# tomato-single-cell.net
KiCad netlist of a schematic drawn in EAGLE
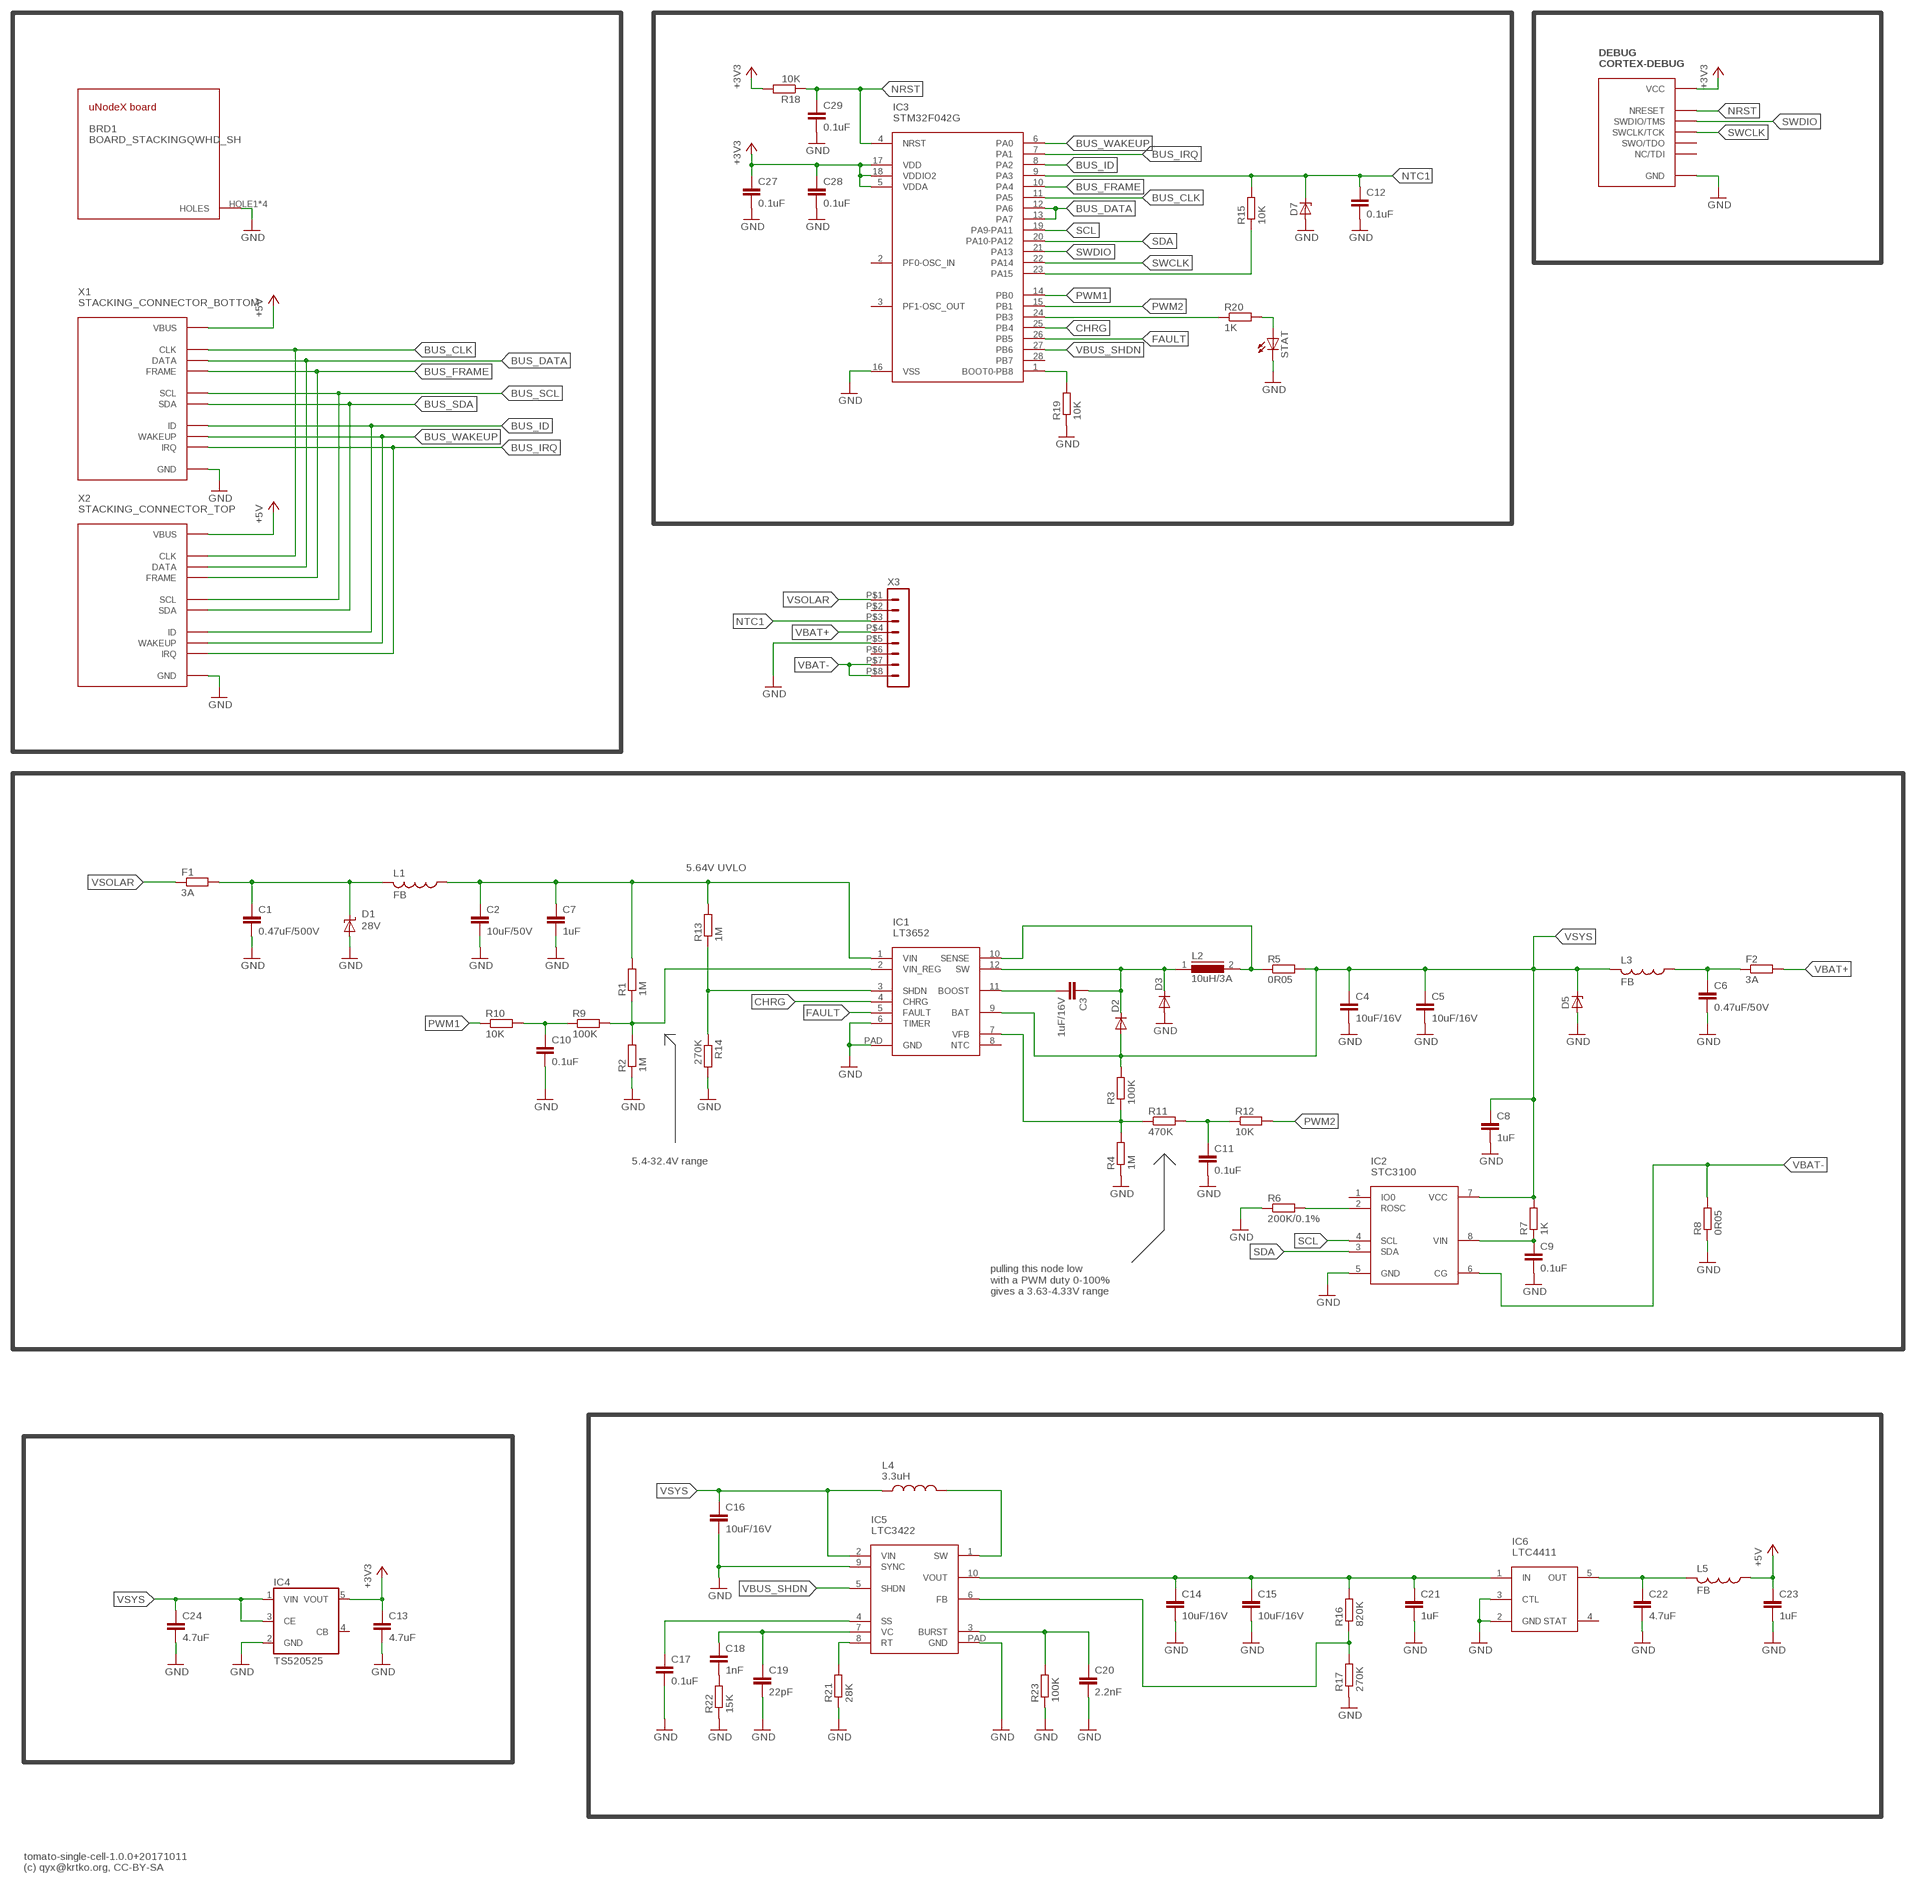
[diagram p0: schematic, sheet 1]

(export (version "E")
  (design (tool "Eeschema 10.0.6"))
  (components
    (comp (ref "BRD1")
      (value "BOARD_STACKINGQWHD_SH")
      (footprint "eagle-import:QWHD_SHARP_CORNERS")
      (libsource (lib "eagle-import") (part "BOARD_STACKINGQWHD_SH"))
    )
    (comp (ref "C1")
      (value "0.47uF/500V")
      (footprint "eagle-import:C1206")
      (libsource (lib "eagle-import") (part "C-EUC1206"))
    )
    (comp (ref "C2")
      (value "10uF/50V")
      (footprint "eagle-import:C2220K")
      (libsource (lib "eagle-import") (part "C-EUC2220K"))
    )
    (comp (ref "C3")
      (value "1uF/16V")
      (footprint "eagle-import:C0805")
      (libsource (lib "eagle-import") (part "C-EUC0805"))
    )
    (comp (ref "C4")
      (value "10uF/16V")
      (footprint "eagle-import:C1206")
      (libsource (lib "eagle-import") (part "C-EUC1206"))
    )
    (comp (ref "C5")
      (value "10uF/16V")
      (footprint "eagle-import:C1206")
      (libsource (lib "eagle-import") (part "C-EUC1206"))
    )
    (comp (ref "C6")
      (value "0.47uF/50V")
      (footprint "eagle-import:C0805")
      (libsource (lib "eagle-import") (part "C-EUC0805"))
    )
    (comp (ref "C7")
      (value "1uF")
      (footprint "eagle-import:C0805")
      (libsource (lib "eagle-import") (part "C-EUC0805"))
    )
    (comp (ref "C8")
      (value "1uF")
      (footprint "eagle-import:C0603")
      (libsource (lib "eagle-import") (part "C-EUC0603"))
    )
    (comp (ref "C9")
      (value "0.1uF")
      (footprint "eagle-import:C0603")
      (libsource (lib "eagle-import") (part "C-EUC0603"))
    )
    (comp (ref "C10")
      (value "0.1uF")
      (footprint "eagle-import:C0603")
      (libsource (lib "eagle-import") (part "C-EUC0603"))
    )
    (comp (ref "C11")
      (value "0.1uF")
      (footprint "eagle-import:C0603")
      (libsource (lib "eagle-import") (part "C-EUC0603"))
    )
    (comp (ref "C12")
      (value "0.1uF")
      (footprint "eagle-import:C0603")
      (libsource (lib "eagle-import") (part "C-EUC0603"))
    )
    (comp (ref "C13")
      (value "4.7uF")
      (footprint "eagle-import:C0805")
      (libsource (lib "eagle-import") (part "C-EUC0805"))
    )
    (comp (ref "C14")
      (value "10uF/16V")
      (footprint "eagle-import:C1206")
      (libsource (lib "eagle-import") (part "C-EUC1206"))
    )
    (comp (ref "C15")
      (value "10uF/16V")
      (footprint "eagle-import:C1206")
      (libsource (lib "eagle-import") (part "C-EUC1206"))
    )
    (comp (ref "C16")
      (value "10uF/16V")
      (footprint "eagle-import:C1206")
      (libsource (lib "eagle-import") (part "C-EUC1206"))
    )
    (comp (ref "C17")
      (value "0.1uF")
      (footprint "eagle-import:C0603")
      (libsource (lib "eagle-import") (part "C-EUC0603"))
    )
    (comp (ref "C18")
      (value "1nF")
      (footprint "eagle-import:C0603")
      (libsource (lib "eagle-import") (part "C-EUC0603"))
    )
    (comp (ref "C19")
      (value "22pF")
      (footprint "eagle-import:C0603")
      (libsource (lib "eagle-import") (part "C-EUC0603"))
    )
    (comp (ref "C20")
      (value "2.2nF")
      (footprint "eagle-import:C0603")
      (libsource (lib "eagle-import") (part "C-EUC0603"))
    )
    (comp (ref "C21")
      (value "1uF")
      (footprint "eagle-import:C0805")
      (libsource (lib "eagle-import") (part "C-EUC0805"))
    )
    (comp (ref "C22")
      (value "4.7uF")
      (footprint "eagle-import:C0805")
      (libsource (lib "eagle-import") (part "C-EUC0805"))
    )
    (comp (ref "C23")
      (value "1uF")
      (footprint "eagle-import:C0805")
      (libsource (lib "eagle-import") (part "C-EUC0805"))
    )
    (comp (ref "C24")
      (value "4.7uF")
      (footprint "eagle-import:C0805")
      (libsource (lib "eagle-import") (part "C-EUC0805"))
    )
    (comp (ref "C27")
      (value "0.1uF")
      (footprint "eagle-import:C0603")
      (libsource (lib "eagle-import") (part "C-EUC0603"))
    )
    (comp (ref "C28")
      (value "0.1uF")
      (footprint "eagle-import:C0603")
      (libsource (lib "eagle-import") (part "C-EUC0603"))
    )
    (comp (ref "C29")
      (value "0.1uF")
      (footprint "eagle-import:C0603")
      (libsource (lib "eagle-import") (part "C-EUC0603"))
    )
    (comp (ref "D1")
      (value "28V")
      (footprint "eagle-import:SMBJ")
      (libsource (lib "eagle-import") (part "SUPPRESSOR-SMBJ"))
    )
    (comp (ref "D2")
      (value "DIODE-SOD323-W")
      (footprint "eagle-import:SOD323-W")
      (libsource (lib "eagle-import") (part "DIODE-SOD323-W"))
    )
    (comp (ref "D3")
      (value "DIODE-SOD323-W")
      (footprint "eagle-import:SOD323-W")
      (libsource (lib "eagle-import") (part "DIODE-SOD323-W"))
    )
    (comp (ref "D5")
      (value "ZENER-DIODESOT23")
      (footprint "eagle-import:SOT23")
      (libsource (lib "eagle-import") (part "ZENER-DIODESOT23"))
    )
    (comp (ref "D7")
      (value "ZENER-DIODESOT23")
      (footprint "eagle-import:SOT23")
      (libsource (lib "eagle-import") (part "ZENER-DIODESOT23"))
    )
    (comp (ref "DEBUG")
      (value "CORTEX-DEBUG")
      (footprint "eagle-import:CORTEX-DEBUG")
      (libsource (lib "eagle-import") (part "CORTEX-DEBUG"))
    )
    (comp (ref "F1")
      (value "3A")
      (footprint "eagle-import:R1206")
      (libsource (lib "eagle-import") (part "R-EU_R1206"))
    )
    (comp (ref "F2")
      (value "3A")
      (footprint "eagle-import:R1206")
      (libsource (lib "eagle-import") (part "R-EU_R1206"))
    )
    (comp (ref "IC1")
      (value "LT3652")
      (footprint "eagle-import:MSOP12-PAD")
      (libsource (lib "eagle-import") (part "LT3652"))
    )
    (comp (ref "IC2")
      (value "STC3100")
      (footprint "eagle-import:MSOP8")
      (libsource (lib "eagle-import") (part "STC3100"))
    )
    (comp (ref "IC3")
      (value "STM32F042G")
      (footprint "eagle-import:UFQFPN28")
      (libsource (lib "eagle-import") (part "STM32F042G"))
    )
    (comp (ref "IC4")
      (value "TS520525")
      (footprint "eagle-import:SOT25")
      (libsource (lib "eagle-import") (part "TS520525"))
    )
    (comp (ref "IC5")
      (value "LTC3422")
      (footprint "eagle-import:DFN10-3X3")
      (libsource (lib "eagle-import") (part "LTC3422"))
    )
    (comp (ref "IC6")
      (value "LTC4411")
      (footprint "eagle-import:SOT23-5")
      (libsource (lib "eagle-import") (part "LTC4411"))
    )
    (comp (ref "L1")
      (value "FB")
      (footprint "eagle-import:L3216C")
      (libsource (lib "eagle-import") (part "L-USL3216C"))
    )
    (comp (ref "L2")
      (value "10uH/3A")
      (footprint "eagle-import:DR74")
      (libsource (lib "eagle-import") (part "DR74"))
    )
    (comp (ref "L3")
      (value "FB")
      (footprint "eagle-import:L3216C")
      (libsource (lib "eagle-import") (part "L-USL3216C"))
    )
    (comp (ref "L4")
      (value "3.3uH")
      (footprint "eagle-import:XAL50XX")
      (libsource (lib "eagle-import") (part "XAL50XX"))
    )
    (comp (ref "L5")
      (value "FB")
      (footprint "eagle-import:L3216C")
      (libsource (lib "eagle-import") (part "L-USL3216C"))
    )
    (comp (ref "R1")
      (value "1M")
      (footprint "eagle-import:R0603")
      (libsource (lib "eagle-import") (part "R-EU_R0603"))
    )
    (comp (ref "R2")
      (value "1M")
      (footprint "eagle-import:R0603")
      (libsource (lib "eagle-import") (part "R-EU_R0603"))
    )
    (comp (ref "R3")
      (value "100K")
      (footprint "eagle-import:R0603")
      (libsource (lib "eagle-import") (part "R-EU_R0603"))
    )
    (comp (ref "R4")
      (value "1M")
      (footprint "eagle-import:R0603")
      (libsource (lib "eagle-import") (part "R-EU_R0603"))
    )
    (comp (ref "R5")
      (value "0R05")
      (footprint "eagle-import:R1206")
      (libsource (lib "eagle-import") (part "R-EU_R1206"))
    )
    (comp (ref "R6")
      (value "200K/0.1%")
      (footprint "eagle-import:R0603")
      (libsource (lib "eagle-import") (part "R-EU_R0603"))
    )
    (comp (ref "R7")
      (value "1K")
      (footprint "eagle-import:R0603")
      (libsource (lib "eagle-import") (part "R-EU_R0603"))
    )
    (comp (ref "R8")
      (value "0R05")
      (footprint "eagle-import:R1206")
      (libsource (lib "eagle-import") (part "R-EU_R1206"))
    )
    (comp (ref "R9")
      (value "100K")
      (footprint "eagle-import:R0603")
      (libsource (lib "eagle-import") (part "R-EU_R0603"))
    )
    (comp (ref "R10")
      (value "10K")
      (footprint "eagle-import:R0603")
      (libsource (lib "eagle-import") (part "R-EU_R0603"))
    )
    (comp (ref "R11")
      (value "470K")
      (footprint "eagle-import:R0603")
      (libsource (lib "eagle-import") (part "R-EU_R0603"))
    )
    (comp (ref "R12")
      (value "10K")
      (footprint "eagle-import:R0603")
      (libsource (lib "eagle-import") (part "R-EU_R0603"))
    )
    (comp (ref "R13")
      (value "1M")
      (footprint "eagle-import:R0603")
      (libsource (lib "eagle-import") (part "R-EU_R0603"))
    )
    (comp (ref "R14")
      (value "270K")
      (footprint "eagle-import:R0603")
      (libsource (lib "eagle-import") (part "R-EU_R0603"))
    )
    (comp (ref "R15")
      (value "10K")
      (footprint "eagle-import:R0603")
      (libsource (lib "eagle-import") (part "R-EU_R0603"))
    )
    (comp (ref "R16")
      (value "820K")
      (footprint "eagle-import:R0603")
      (libsource (lib "eagle-import") (part "R-EU_R0603"))
    )
    (comp (ref "R17")
      (value "270K")
      (footprint "eagle-import:R0603")
      (libsource (lib "eagle-import") (part "R-EU_R0603"))
    )
    (comp (ref "R18")
      (value "10K")
      (footprint "eagle-import:R0603")
      (libsource (lib "eagle-import") (part "R-EU_R0603"))
    )
    (comp (ref "R19")
      (value "10K")
      (footprint "eagle-import:R0603")
      (libsource (lib "eagle-import") (part "R-EU_R0603"))
    )
    (comp (ref "R20")
      (value "1K")
      (footprint "eagle-import:R0603")
      (libsource (lib "eagle-import") (part "R-EU_R0603"))
    )
    (comp (ref "R21")
      (value "28K")
      (footprint "eagle-import:R0603")
      (libsource (lib "eagle-import") (part "R-EU_R0603"))
    )
    (comp (ref "R22")
      (value "15K")
      (footprint "eagle-import:R0603")
      (libsource (lib "eagle-import") (part "R-EU_R0603"))
    )
    (comp (ref "R23")
      (value "100K")
      (footprint "eagle-import:R0603")
      (libsource (lib "eagle-import") (part "R-EU_R0603"))
    )
    (comp (ref "STAT")
      (value "LEDCHIPLED_0805")
      (footprint "eagle-import:CHIPLED_0805")
      (libsource (lib "eagle-import") (part "LEDCHIPLED_0805"))
    )
    (comp (ref "X1")
      (value "STACKING_CONNECTOR_BOTTOM")
      (footprint "eagle-import:HAR-FLEX-BOTTOM-12P")
      (libsource (lib "eagle-import") (part "STACKING_CONNECTOR_BOTTOM"))
    )
    (comp (ref "X2")
      (value "STACKING_CONNECTOR_TOP")
      (footprint "eagle-import:HAR-FLEX-TOP-12P")
      (libsource (lib "eagle-import") (part "STACKING_CONNECTOR_TOP"))
    )
    (comp (ref "X3")
      (value "HEADER_POS8_43045-0800")
      (footprint "eagle-import:43045-0800")
      (libsource (lib "eagle-import") (part "HEADER_POS8_?43045-0800"))
    )
  )
  (nets
    (net (code "1") (name "+3V3") (class "Default")
      (node (ref "C13") (pin "1") (pinfunction "1_1") (pintype "passive"))
      (node (ref "C27") (pin "1") (pinfunction "1_1") (pintype "passive"))
      (node (ref "C28") (pin "1") (pinfunction "1_1") (pintype "passive"))
      (node (ref "DEBUG") (pin "VCC") (pinfunction "VCC_VCC") (pintype "bidirectional"))
      (node (ref "IC3") (pin "17") (pinfunction "VDD_17") (pintype "bidirectional"))
      (node (ref "IC3") (pin "18") (pinfunction "VDDIO2_18") (pintype "bidirectional"))
      (node (ref "IC3") (pin "5") (pinfunction "VDDA_5") (pintype "bidirectional"))
      (node (ref "IC4") (pin "5") (pinfunction "VOUT_5") (pintype "passive"))
      (node (ref "R18") (pin "2") (pinfunction "2_2") (pintype "passive"))
    )
    (net (code "2") (name "+5V") (class "Default")
      (node (ref "C23") (pin "1") (pinfunction "1_1") (pintype "passive"))
      (node (ref "L5") (pin "1") (pinfunction "1_1") (pintype "passive"))
      (node (ref "X1") (pin "VBUS") (pinfunction "VBUS_VBUS") (pintype "bidirectional"))
      (node (ref "X2") (pin "VBUS") (pinfunction "VBUS_VBUS") (pintype "bidirectional"))
    )
    (net (code "3") (name "BUS_CLK") (class "Default")
      (node (ref "IC3") (pin "11") (pinfunction "PA5_11") (pintype "bidirectional"))
      (node (ref "X1") (pin "CLK") (pinfunction "CLK_CLK") (pintype "bidirectional"))
      (node (ref "X2") (pin "CLK") (pinfunction "CLK_CLK") (pintype "bidirectional"))
    )
    (net (code "4") (name "BUS_DATA") (class "Default")
      (node (ref "IC3") (pin "12") (pinfunction "PA6_12") (pintype "bidirectional"))
      (node (ref "IC3") (pin "13") (pinfunction "PA7_13") (pintype "bidirectional"))
      (node (ref "X1") (pin "DATA") (pinfunction "DATA_DATA") (pintype "bidirectional"))
      (node (ref "X2") (pin "DATA") (pinfunction "DATA_DATA") (pintype "bidirectional"))
    )
    (net (code "5") (name "BUS_FRAME") (class "Default")
      (node (ref "IC3") (pin "10") (pinfunction "PA4_10") (pintype "bidirectional"))
      (node (ref "X1") (pin "FRAME") (pinfunction "FRAME_FRAME") (pintype "bidirectional"))
      (node (ref "X2") (pin "FRAME") (pinfunction "FRAME_FRAME") (pintype "bidirectional"))
    )
    (net (code "6") (name "BUS_ID") (class "Default")
      (node (ref "IC3") (pin "8") (pinfunction "PA2_8") (pintype "bidirectional"))
      (node (ref "X1") (pin "ID") (pinfunction "ID_ID") (pintype "bidirectional"))
      (node (ref "X2") (pin "ID") (pinfunction "ID_ID") (pintype "bidirectional"))
    )
    (net (code "7") (name "BUS_IRQ") (class "Default")
      (node (ref "IC3") (pin "7") (pinfunction "PA1_7") (pintype "bidirectional"))
      (node (ref "X1") (pin "IRQ") (pinfunction "IRQ_IRQ") (pintype "bidirectional"))
      (node (ref "X2") (pin "IRQ") (pinfunction "IRQ_IRQ") (pintype "bidirectional"))
    )
    (net (code "8") (name "BUS_SCL") (class "Default")
      (node (ref "X1") (pin "SCL") (pinfunction "SCL_SCL") (pintype "bidirectional"))
      (node (ref "X2") (pin "SCL") (pinfunction "SCL_SCL") (pintype "bidirectional"))
    )
    (net (code "9") (name "BUS_SDA") (class "Default")
      (node (ref "X1") (pin "SDA") (pinfunction "SDA_SDA") (pintype "bidirectional"))
      (node (ref "X2") (pin "SDA") (pinfunction "SDA_SDA") (pintype "bidirectional"))
    )
    (net (code "10") (name "BUS_WAKEUP") (class "Default")
      (node (ref "IC3") (pin "6") (pinfunction "PA0_6") (pintype "bidirectional"))
      (node (ref "X1") (pin "WAKEUP") (pinfunction "WAKEUP_WAKEUP") (pintype "bidirectional"))
      (node (ref "X2") (pin "WAKEUP") (pinfunction "WAKEUP_WAKEUP") (pintype "bidirectional"))
    )
    (net (code "11") (name "CHRG") (class "Default")
      (node (ref "IC1") (pin "4") (pinfunction "CHRG_4") (pintype "bidirectional"))
      (node (ref "IC3") (pin "25") (pinfunction "PB4_25") (pintype "bidirectional"))
    )
    (net (code "12") (name "FAULT") (class "Default")
      (node (ref "IC1") (pin "5") (pinfunction "FAULT_5") (pintype "bidirectional"))
      (node (ref "IC3") (pin "26") (pinfunction "PB5_26") (pintype "bidirectional"))
    )
    (net (code "13") (name "GND") (class "Default")
      (node (ref "BRD1") (pin "HOLE1") (pinfunction "HOLES_HOLE1") (pintype "bidirectional"))
      (node (ref "BRD1") (pin "HOLE2") (pinfunction "HOLES_HOLE2") (pintype "bidirectional"))
      (node (ref "BRD1") (pin "HOLE3") (pinfunction "HOLES_HOLE3") (pintype "bidirectional"))
      (node (ref "BRD1") (pin "HOLE4") (pinfunction "HOLES_HOLE4") (pintype "bidirectional"))
      (node (ref "C1") (pin "2") (pinfunction "2_2") (pintype "passive"))
      (node (ref "C10") (pin "2") (pinfunction "2_2") (pintype "passive"))
      (node (ref "C11") (pin "2") (pinfunction "2_2") (pintype "passive"))
      (node (ref "C12") (pin "2") (pinfunction "2_2") (pintype "passive"))
      (node (ref "C13") (pin "2") (pinfunction "2_2") (pintype "passive"))
      (node (ref "C14") (pin "2") (pinfunction "2_2") (pintype "passive"))
      (node (ref "C15") (pin "2") (pinfunction "2_2") (pintype "passive"))
      (node (ref "C16") (pin "2") (pinfunction "2_2") (pintype "passive"))
      (node (ref "C17") (pin "2") (pinfunction "2_2") (pintype "passive"))
      (node (ref "C19") (pin "2") (pinfunction "2_2") (pintype "passive"))
      (node (ref "C2") (pin "2") (pinfunction "2_2") (pintype "passive"))
      (node (ref "C20") (pin "2") (pinfunction "2_2") (pintype "passive"))
      (node (ref "C21") (pin "2") (pinfunction "2_2") (pintype "passive"))
      (node (ref "C22") (pin "2") (pinfunction "2_2") (pintype "passive"))
      (node (ref "C23") (pin "2") (pinfunction "2_2") (pintype "passive"))
      (node (ref "C24") (pin "2") (pinfunction "2_2") (pintype "passive"))
      (node (ref "C27") (pin "2") (pinfunction "2_2") (pintype "passive"))
      (node (ref "C28") (pin "2") (pinfunction "2_2") (pintype "passive"))
      (node (ref "C29") (pin "2") (pinfunction "2_2") (pintype "passive"))
      (node (ref "C4") (pin "2") (pinfunction "2_2") (pintype "passive"))
      (node (ref "C5") (pin "2") (pinfunction "2_2") (pintype "passive"))
      (node (ref "C6") (pin "2") (pinfunction "2_2") (pintype "passive"))
      (node (ref "C7") (pin "2") (pinfunction "2_2") (pintype "passive"))
      (node (ref "C8") (pin "2") (pinfunction "2_2") (pintype "passive"))
      (node (ref "C9") (pin "2") (pinfunction "2_2") (pintype "passive"))
      (node (ref "D1") (pin "A") (pinfunction "A_A") (pintype "passive"))
      (node (ref "D3") (pin "A") (pinfunction "A_A") (pintype "passive"))
      (node (ref "D5") (pin "1") (pinfunction "A_1") (pintype "passive"))
      (node (ref "D7") (pin "1") (pinfunction "A_1") (pintype "passive"))
      (node (ref "DEBUG") (pin "GND1") (pinfunction "GND_GND1") (pintype "bidirectional"))
      (node (ref "DEBUG") (pin "GND2") (pinfunction "GND_GND2") (pintype "bidirectional"))
      (node (ref "DEBUG") (pin "GND_DETECT") (pinfunction "GND_GND_DETECT") (pintype "bidirectional"))
      (node (ref "IC1") (pin "6") (pinfunction "TIMER_6") (pintype "bidirectional"))
      (node (ref "IC1") (pin "PAD") (pinfunction "GND_PAD") (pintype "bidirectional"))
      (node (ref "IC2") (pin "5") (pinfunction "GND_5") (pintype "power_in"))
      (node (ref "IC3") (pin "16") (pinfunction "VSS_16") (pintype "bidirectional"))
      (node (ref "IC4") (pin "2") (pinfunction "GND_2") (pintype "passive"))
      (node (ref "IC5") (pin "9") (pinfunction "SYNC_9") (pintype "bidirectional"))
      (node (ref "IC5") (pin "PAD") (pinfunction "GND_PAD") (pintype "bidirectional"))
      (node (ref "IC6") (pin "2") (pinfunction "GND_2") (pintype "bidirectional"))
      (node (ref "IC6") (pin "3") (pinfunction "CTL_3") (pintype "bidirectional"))
      (node (ref "R14") (pin "2") (pinfunction "2_2") (pintype "passive"))
      (node (ref "R17") (pin "1") (pinfunction "1_1") (pintype "passive"))
      (node (ref "R19") (pin "1") (pinfunction "1_1") (pintype "passive"))
      (node (ref "R2") (pin "1") (pinfunction "1_1") (pintype "passive"))
      (node (ref "R21") (pin "1") (pinfunction "1_1") (pintype "passive"))
      (node (ref "R22") (pin "1") (pinfunction "1_1") (pintype "passive"))
      (node (ref "R23") (pin "1") (pinfunction "1_1") (pintype "passive"))
      (node (ref "R4") (pin "1") (pinfunction "1_1") (pintype "passive"))
      (node (ref "R6") (pin "1") (pinfunction "1_1") (pintype "passive"))
      (node (ref "R8") (pin "1") (pinfunction "1_1") (pintype "passive"))
      (node (ref "STAT") (pin "C") (pinfunction "C_C") (pintype "passive"))
      (node (ref "X1") (pin "GND1") (pinfunction "GND_GND1") (pintype "bidirectional"))
      (node (ref "X1") (pin "GND2") (pinfunction "GND_GND2") (pintype "bidirectional"))
      (node (ref "X1") (pin "GND3") (pinfunction "GND_GND3") (pintype "bidirectional"))
      (node (ref "X1") (pin "H1") (pinfunction "GND_H1") (pintype "bidirectional"))
      (node (ref "X1") (pin "H2") (pinfunction "GND_H2") (pintype "bidirectional"))
      (node (ref "X1") (pin "H3") (pinfunction "GND_H3") (pintype "bidirectional"))
      (node (ref "X1") (pin "H4") (pinfunction "GND_H4") (pintype "bidirectional"))
      (node (ref "X2") (pin "GND1") (pinfunction "GND_GND1") (pintype "bidirectional"))
      (node (ref "X2") (pin "GND2") (pinfunction "GND_GND2") (pintype "bidirectional"))
      (node (ref "X2") (pin "GND3") (pinfunction "GND_GND3") (pintype "bidirectional"))
      (node (ref "X2") (pin "H1") (pinfunction "GND_H1") (pintype "bidirectional"))
      (node (ref "X2") (pin "H2") (pinfunction "GND_H2") (pintype "bidirectional"))
      (node (ref "X2") (pin "H3") (pinfunction "GND_H3") (pintype "bidirectional"))
      (node (ref "X2") (pin "H4") (pinfunction "GND_H4") (pintype "bidirectional"))
      (node (ref "X3") (pin "P$5") (pinfunction "5_P$5") (pintype "passive"))
    )
    (net (code "14") (name "NRST") (class "Default")
      (node (ref "C29") (pin "1") (pinfunction "1_1") (pintype "passive"))
      (node (ref "DEBUG") (pin "NRESET") (pinfunction "NRESET_NRESET") (pintype "bidirectional"))
      (node (ref "IC3") (pin "4") (pinfunction "NRST_4") (pintype "bidirectional"))
      (node (ref "R18") (pin "1") (pinfunction "1_1") (pintype "passive"))
    )
    (net (code "15") (name "NTC1") (class "Default")
      (node (ref "C12") (pin "1") (pinfunction "1_1") (pintype "passive"))
      (node (ref "D7") (pin "3") (pinfunction "C_3") (pintype "passive"))
      (node (ref "IC3") (pin "9") (pinfunction "PA3_9") (pintype "bidirectional"))
      (node (ref "R15") (pin "2") (pinfunction "2_2") (pintype "passive"))
      (node (ref "X3") (pin "P$3") (pinfunction "3_P$3") (pintype "passive"))
    )
    (net (code "16") (name "Net-(C1-Pad1)") (class "Default")
      (node (ref "C1") (pin "1") (pinfunction "1_1") (pintype "passive"))
      (node (ref "D1") (pin "C") (pinfunction "C_C") (pintype "passive"))
      (node (ref "F1") (pin "2") (pinfunction "2_2") (pintype "passive"))
      (node (ref "L1") (pin "2") (pinfunction "2_2") (pintype "passive"))
    )
    (net (code "17") (name "Net-(C6-Pad1)") (class "Default")
      (node (ref "C6") (pin "1") (pinfunction "1_1") (pintype "passive"))
      (node (ref "F2") (pin "1") (pinfunction "1_1") (pintype "passive"))
      (node (ref "L3") (pin "1") (pinfunction "1_1") (pintype "passive"))
    )
    (net (code "18") (name "Net-(C10-Pad1)") (class "Default")
      (node (ref "C10") (pin "1") (pinfunction "1_1") (pintype "passive"))
      (node (ref "R10") (pin "2") (pinfunction "2_2") (pintype "passive"))
      (node (ref "R9") (pin "1") (pinfunction "1_1") (pintype "passive"))
    )
    (net (code "19") (name "Net-(C11-Pad1)") (class "Default")
      (node (ref "C11") (pin "1") (pinfunction "1_1") (pintype "passive"))
      (node (ref "R11") (pin "2") (pinfunction "2_2") (pintype "passive"))
      (node (ref "R12") (pin "1") (pinfunction "1_1") (pintype "passive"))
    )
    (net (code "20") (name "Net-(C18-Pad2)") (class "Default")
      (node (ref "C18") (pin "2") (pinfunction "2_2") (pintype "passive"))
      (node (ref "R22") (pin "2") (pinfunction "2_2") (pintype "passive"))
    )
    (net (code "21") (name "Net-(IC1-BOOST)") (class "Default")
      (node (ref "C3") (pin "2") (pinfunction "2_2") (pintype "passive"))
      (node (ref "IC1") (pin "11") (pinfunction "BOOST_11") (pintype "bidirectional"))
    )
    (net (code "22") (name "Net-(IC1-SENSE)") (class "Default")
      (node (ref "IC1") (pin "10") (pinfunction "SENSE_10") (pintype "bidirectional"))
      (node (ref "L2") (pin "2") (pinfunction "2_2") (pintype "passive"))
      (node (ref "R5") (pin "1") (pinfunction "1_1") (pintype "passive"))
    )
    (net (code "23") (name "Net-(IC1-SHDN)") (class "Default")
      (node (ref "IC1") (pin "3") (pinfunction "SHDN_3") (pintype "bidirectional"))
      (node (ref "R13") (pin "1") (pinfunction "1_1") (pintype "passive"))
      (node (ref "R14") (pin "1") (pinfunction "1_1") (pintype "passive"))
    )
    (net (code "24") (name "Net-(IC1-SW)") (class "Default")
      (node (ref "C3") (pin "1") (pinfunction "1_1") (pintype "passive"))
      (node (ref "D2") (pin "C") (pinfunction "C_C") (pintype "passive"))
      (node (ref "D3") (pin "C") (pinfunction "C_C") (pintype "passive"))
      (node (ref "IC1") (pin "12") (pinfunction "SW_12") (pintype "bidirectional"))
      (node (ref "L2") (pin "1") (pinfunction "1_1") (pintype "passive"))
    )
    (net (code "25") (name "Net-(IC1-VFB)") (class "Default")
      (node (ref "IC1") (pin "7") (pinfunction "VFB_7") (pintype "bidirectional"))
      (node (ref "R11") (pin "1") (pinfunction "1_1") (pintype "passive"))
      (node (ref "R3") (pin "1") (pinfunction "1_1") (pintype "passive"))
      (node (ref "R4") (pin "2") (pinfunction "2_2") (pintype "passive"))
    )
    (net (code "26") (name "Net-(IC1-VIN)") (class "Default")
      (node (ref "C2") (pin "1") (pinfunction "1_1") (pintype "passive"))
      (node (ref "C7") (pin "1") (pinfunction "1_1") (pintype "passive"))
      (node (ref "IC1") (pin "1") (pinfunction "VIN_1") (pintype "bidirectional"))
      (node (ref "L1") (pin "1") (pinfunction "1_1") (pintype "passive"))
      (node (ref "R1") (pin "2") (pinfunction "2_2") (pintype "passive"))
      (node (ref "R13") (pin "2") (pinfunction "2_2") (pintype "passive"))
    )
    (net (code "27") (name "Net-(IC1-VIN_REG)") (class "Default")
      (node (ref "IC1") (pin "2") (pinfunction "VIN_REG_2") (pintype "bidirectional"))
      (node (ref "R1") (pin "1") (pinfunction "1_1") (pintype "passive"))
      (node (ref "R2") (pin "2") (pinfunction "2_2") (pintype "passive"))
      (node (ref "R9") (pin "2") (pinfunction "2_2") (pintype "passive"))
    )
    (net (code "28") (name "Net-(IC2-ROSC)") (class "Default")
      (node (ref "IC2") (pin "2") (pinfunction "ROSC_2") (pintype "bidirectional"))
      (node (ref "R6") (pin "2") (pinfunction "2_2") (pintype "passive"))
    )
    (net (code "29") (name "Net-(IC2-VIN)") (class "Default")
      (node (ref "C9") (pin "1") (pinfunction "1_1") (pintype "passive"))
      (node (ref "IC2") (pin "8") (pinfunction "VIN_8") (pintype "input"))
      (node (ref "R7") (pin "1") (pinfunction "1_1") (pintype "passive"))
    )
    (net (code "30") (name "Net-(IC3-BOOT0-PB8)") (class "Default")
      (node (ref "IC3") (pin "1") (pinfunction "BOOT0-PB8_1") (pintype "bidirectional"))
      (node (ref "R19") (pin "2") (pinfunction "2_2") (pintype "passive"))
    )
    (net (code "31") (name "Net-(IC3-PA15)") (class "Default")
      (node (ref "IC3") (pin "23") (pinfunction "PA15_23") (pintype "bidirectional"))
      (node (ref "R15") (pin "1") (pinfunction "1_1") (pintype "passive"))
    )
    (net (code "32") (name "Net-(IC3-PB3)") (class "Default")
      (node (ref "IC3") (pin "24") (pinfunction "PB3_24") (pintype "bidirectional"))
      (node (ref "R20") (pin "1") (pinfunction "1_1") (pintype "passive"))
    )
    (net (code "33") (name "Net-(IC5-BURST)") (class "Default")
      (node (ref "C20") (pin "1") (pinfunction "1_1") (pintype "passive"))
      (node (ref "IC5") (pin "3") (pinfunction "BURST_3") (pintype "bidirectional"))
      (node (ref "R23") (pin "2") (pinfunction "2_2") (pintype "passive"))
    )
    (net (code "34") (name "Net-(IC5-FB)") (class "Default")
      (node (ref "IC5") (pin "6") (pinfunction "FB_6") (pintype "bidirectional"))
      (node (ref "R16") (pin "1") (pinfunction "1_1") (pintype "passive"))
      (node (ref "R17") (pin "2") (pinfunction "2_2") (pintype "passive"))
    )
    (net (code "35") (name "Net-(IC5-RT)") (class "Default")
      (node (ref "IC5") (pin "8") (pinfunction "RT_8") (pintype "bidirectional"))
      (node (ref "R21") (pin "2") (pinfunction "2_2") (pintype "passive"))
    )
    (net (code "36") (name "Net-(IC5-SS)") (class "Default")
      (node (ref "C17") (pin "1") (pinfunction "1_1") (pintype "passive"))
      (node (ref "IC5") (pin "4") (pinfunction "SS_4") (pintype "bidirectional"))
    )
    (net (code "37") (name "Net-(IC5-SW)") (class "Default")
      (node (ref "IC5") (pin "1") (pinfunction "SW_1") (pintype "bidirectional"))
      (node (ref "L4") (pin "2") (pinfunction "2_2") (pintype "passive"))
    )
    (net (code "38") (name "Net-(IC5-VC)") (class "Default")
      (node (ref "C18") (pin "1") (pinfunction "1_1") (pintype "passive"))
      (node (ref "C19") (pin "1") (pinfunction "1_1") (pintype "passive"))
      (node (ref "IC5") (pin "7") (pinfunction "VC_7") (pintype "bidirectional"))
    )
    (net (code "39") (name "Net-(IC5-VOUT)") (class "Default")
      (node (ref "C14") (pin "1") (pinfunction "1_1") (pintype "passive"))
      (node (ref "C15") (pin "1") (pinfunction "1_1") (pintype "passive"))
      (node (ref "C21") (pin "1") (pinfunction "1_1") (pintype "passive"))
      (node (ref "IC5") (pin "10") (pinfunction "VOUT_10") (pintype "bidirectional"))
      (node (ref "IC6") (pin "1") (pinfunction "IN_1") (pintype "bidirectional"))
      (node (ref "R16") (pin "2") (pinfunction "2_2") (pintype "passive"))
    )
    (net (code "40") (name "Net-(IC6-OUT)") (class "Default")
      (node (ref "C22") (pin "1") (pinfunction "1_1") (pintype "passive"))
      (node (ref "IC6") (pin "5") (pinfunction "OUT_5") (pintype "bidirectional"))
      (node (ref "L5") (pin "2") (pinfunction "2_2") (pintype "passive"))
    )
    (net (code "41") (name "Net-(R20-Pad2)") (class "Default")
      (node (ref "R20") (pin "2") (pinfunction "2_2") (pintype "passive"))
      (node (ref "STAT") (pin "A") (pinfunction "A_A") (pintype "passive"))
    )
    (net (code "42") (name "PWM1") (class "Default")
      (node (ref "IC3") (pin "14") (pinfunction "PB0_14") (pintype "bidirectional"))
      (node (ref "R10") (pin "1") (pinfunction "1_1") (pintype "passive"))
    )
    (net (code "43") (name "PWM2") (class "Default")
      (node (ref "IC3") (pin "15") (pinfunction "PB1_15") (pintype "bidirectional"))
      (node (ref "R12") (pin "2") (pinfunction "2_2") (pintype "passive"))
    )
    (net (code "44") (name "SCL") (class "Default")
      (node (ref "IC2") (pin "4") (pinfunction "SCL_4") (pintype "bidirectional"))
      (node (ref "IC3") (pin "19") (pinfunction "PA9-PA11_19") (pintype "bidirectional"))
    )
    (net (code "45") (name "SDA") (class "Default")
      (node (ref "IC2") (pin "3") (pinfunction "SDA_3") (pintype "bidirectional"))
      (node (ref "IC3") (pin "20") (pinfunction "PA10-PA12_20") (pintype "bidirectional"))
    )
    (net (code "46") (name "SWCLK") (class "Default")
      (node (ref "DEBUG") (pin "SWCLK/TCK") (pinfunction "SWCLK/TCK_SWCLK/TCK") (pintype "bidirectional"))
      (node (ref "IC3") (pin "22") (pinfunction "PA14_22") (pintype "bidirectional"))
    )
    (net (code "47") (name "SWDIO") (class "Default")
      (node (ref "DEBUG") (pin "SWDIO/TMS") (pinfunction "SWDIO/TMS_SWDIO/TMS") (pintype "bidirectional"))
      (node (ref "IC3") (pin "21") (pinfunction "PA13_21") (pintype "bidirectional"))
    )
    (net (code "48") (name "VBAT+") (class "Default")
      (node (ref "F2") (pin "2") (pinfunction "2_2") (pintype "passive"))
      (node (ref "X3") (pin "P$4") (pinfunction "4_P$4") (pintype "passive"))
    )
    (net (code "49") (name "VBAT-") (class "Default")
      (node (ref "IC2") (pin "6") (pinfunction "CG_6") (pintype "input"))
      (node (ref "R8") (pin "2") (pinfunction "2_2") (pintype "passive"))
      (node (ref "X3") (pin "P$7") (pinfunction "7_P$7") (pintype "passive"))
      (node (ref "X3") (pin "P$8") (pinfunction "8_P$8") (pintype "passive"))
    )
    (net (code "50") (name "VBUS_SHDN") (class "Default")
      (node (ref "IC3") (pin "27") (pinfunction "PB6_27") (pintype "bidirectional"))
      (node (ref "IC5") (pin "5") (pinfunction "SHDN_5") (pintype "bidirectional"))
    )
    (net (code "51") (name "VSOLAR") (class "Default")
      (node (ref "F1") (pin "1") (pinfunction "1_1") (pintype "passive"))
      (node (ref "X3") (pin "P$1") (pinfunction "1_P$1") (pintype "passive"))
    )
    (net (code "52") (name "VSYS") (class "Default")
      (node (ref "C16") (pin "1") (pinfunction "1_1") (pintype "passive"))
      (node (ref "C24") (pin "1") (pinfunction "1_1") (pintype "passive"))
      (node (ref "C4") (pin "1") (pinfunction "1_1") (pintype "passive"))
      (node (ref "C5") (pin "1") (pinfunction "1_1") (pintype "passive"))
      (node (ref "C8") (pin "1") (pinfunction "1_1") (pintype "passive"))
      (node (ref "D2") (pin "A") (pinfunction "A_A") (pintype "passive"))
      (node (ref "D5") (pin "3") (pinfunction "C_3") (pintype "passive"))
      (node (ref "IC1") (pin "9") (pinfunction "BAT_9") (pintype "bidirectional"))
      (node (ref "IC2") (pin "7") (pinfunction "VCC_7") (pintype "power_in"))
      (node (ref "IC4") (pin "1") (pinfunction "VIN_1") (pintype "input"))
      (node (ref "IC4") (pin "3") (pinfunction "CE_3") (pintype "input"))
      (node (ref "IC5") (pin "2") (pinfunction "VIN_2") (pintype "bidirectional"))
      (node (ref "L3") (pin "2") (pinfunction "2_2") (pintype "passive"))
      (node (ref "L4") (pin "1") (pinfunction "1_1") (pintype "passive"))
      (node (ref "R3") (pin "2") (pinfunction "2_2") (pintype "passive"))
      (node (ref "R5") (pin "2") (pinfunction "2_2") (pintype "passive"))
      (node (ref "R7") (pin "2") (pinfunction "2_2") (pintype "passive"))
    )
    (net (code "53") (name "unconnected-(DEBUG-PadNC{slash}TDI)") (class "Default")
      (node (ref "DEBUG") (pin "NC/TDI") (pinfunction "NC/TDI_NC/TDI") (pintype "bidirectional"))
    )
    (net (code "54") (name "unconnected-(DEBUG-PadSWO{slash}TDO)") (class "Default")
      (node (ref "DEBUG") (pin "SWO/TDO") (pinfunction "SWO/TDO_SWO/TDO") (pintype "bidirectional"))
    )
    (net (code "55") (name "unconnected-(IC1-NTC-Pad8)") (class "Default")
      (node (ref "IC1") (pin "8") (pinfunction "NTC_8") (pintype "bidirectional"))
    )
    (net (code "56") (name "unconnected-(IC2-IO0-Pad1)") (class "Default")
      (node (ref "IC2") (pin "1") (pinfunction "IO0_1") (pintype "bidirectional"))
    )
    (net (code "57") (name "unconnected-(IC3-PB7-Pad28)") (class "Default")
      (node (ref "IC3") (pin "28") (pinfunction "PB7_28") (pintype "bidirectional"))
    )
    (net (code "58") (name "unconnected-(IC3-PF0-OSC_IN-Pad2)") (class "Default")
      (node (ref "IC3") (pin "2") (pinfunction "PF0-OSC_IN_2") (pintype "bidirectional"))
    )
    (net (code "59") (name "unconnected-(IC3-PF1-OSC_OUT-Pad3)") (class "Default")
      (node (ref "IC3") (pin "3") (pinfunction "PF1-OSC_OUT_3") (pintype "bidirectional"))
    )
    (net (code "60") (name "unconnected-(IC4-CB-Pad4)") (class "Default")
      (node (ref "IC4") (pin "4") (pinfunction "CB_4") (pintype "input"))
    )
    (net (code "61") (name "unconnected-(IC6-STAT-Pad4)") (class "Default")
      (node (ref "IC6") (pin "4") (pinfunction "STAT_4") (pintype "bidirectional"))
    )
    (net (code "62") (name "unconnected-(X3-2-PadP$2)") (class "Default")
      (node (ref "X3") (pin "P$2") (pinfunction "2_P$2") (pintype "passive"))
    )
    (net (code "63") (name "unconnected-(X3-6-PadP$6)") (class "Default")
      (node (ref "X3") (pin "P$6") (pinfunction "6_P$6") (pintype "passive"))
    )
  )
)
